# Main.net
KiCad netlist of a schematic drawn in Altium Designer
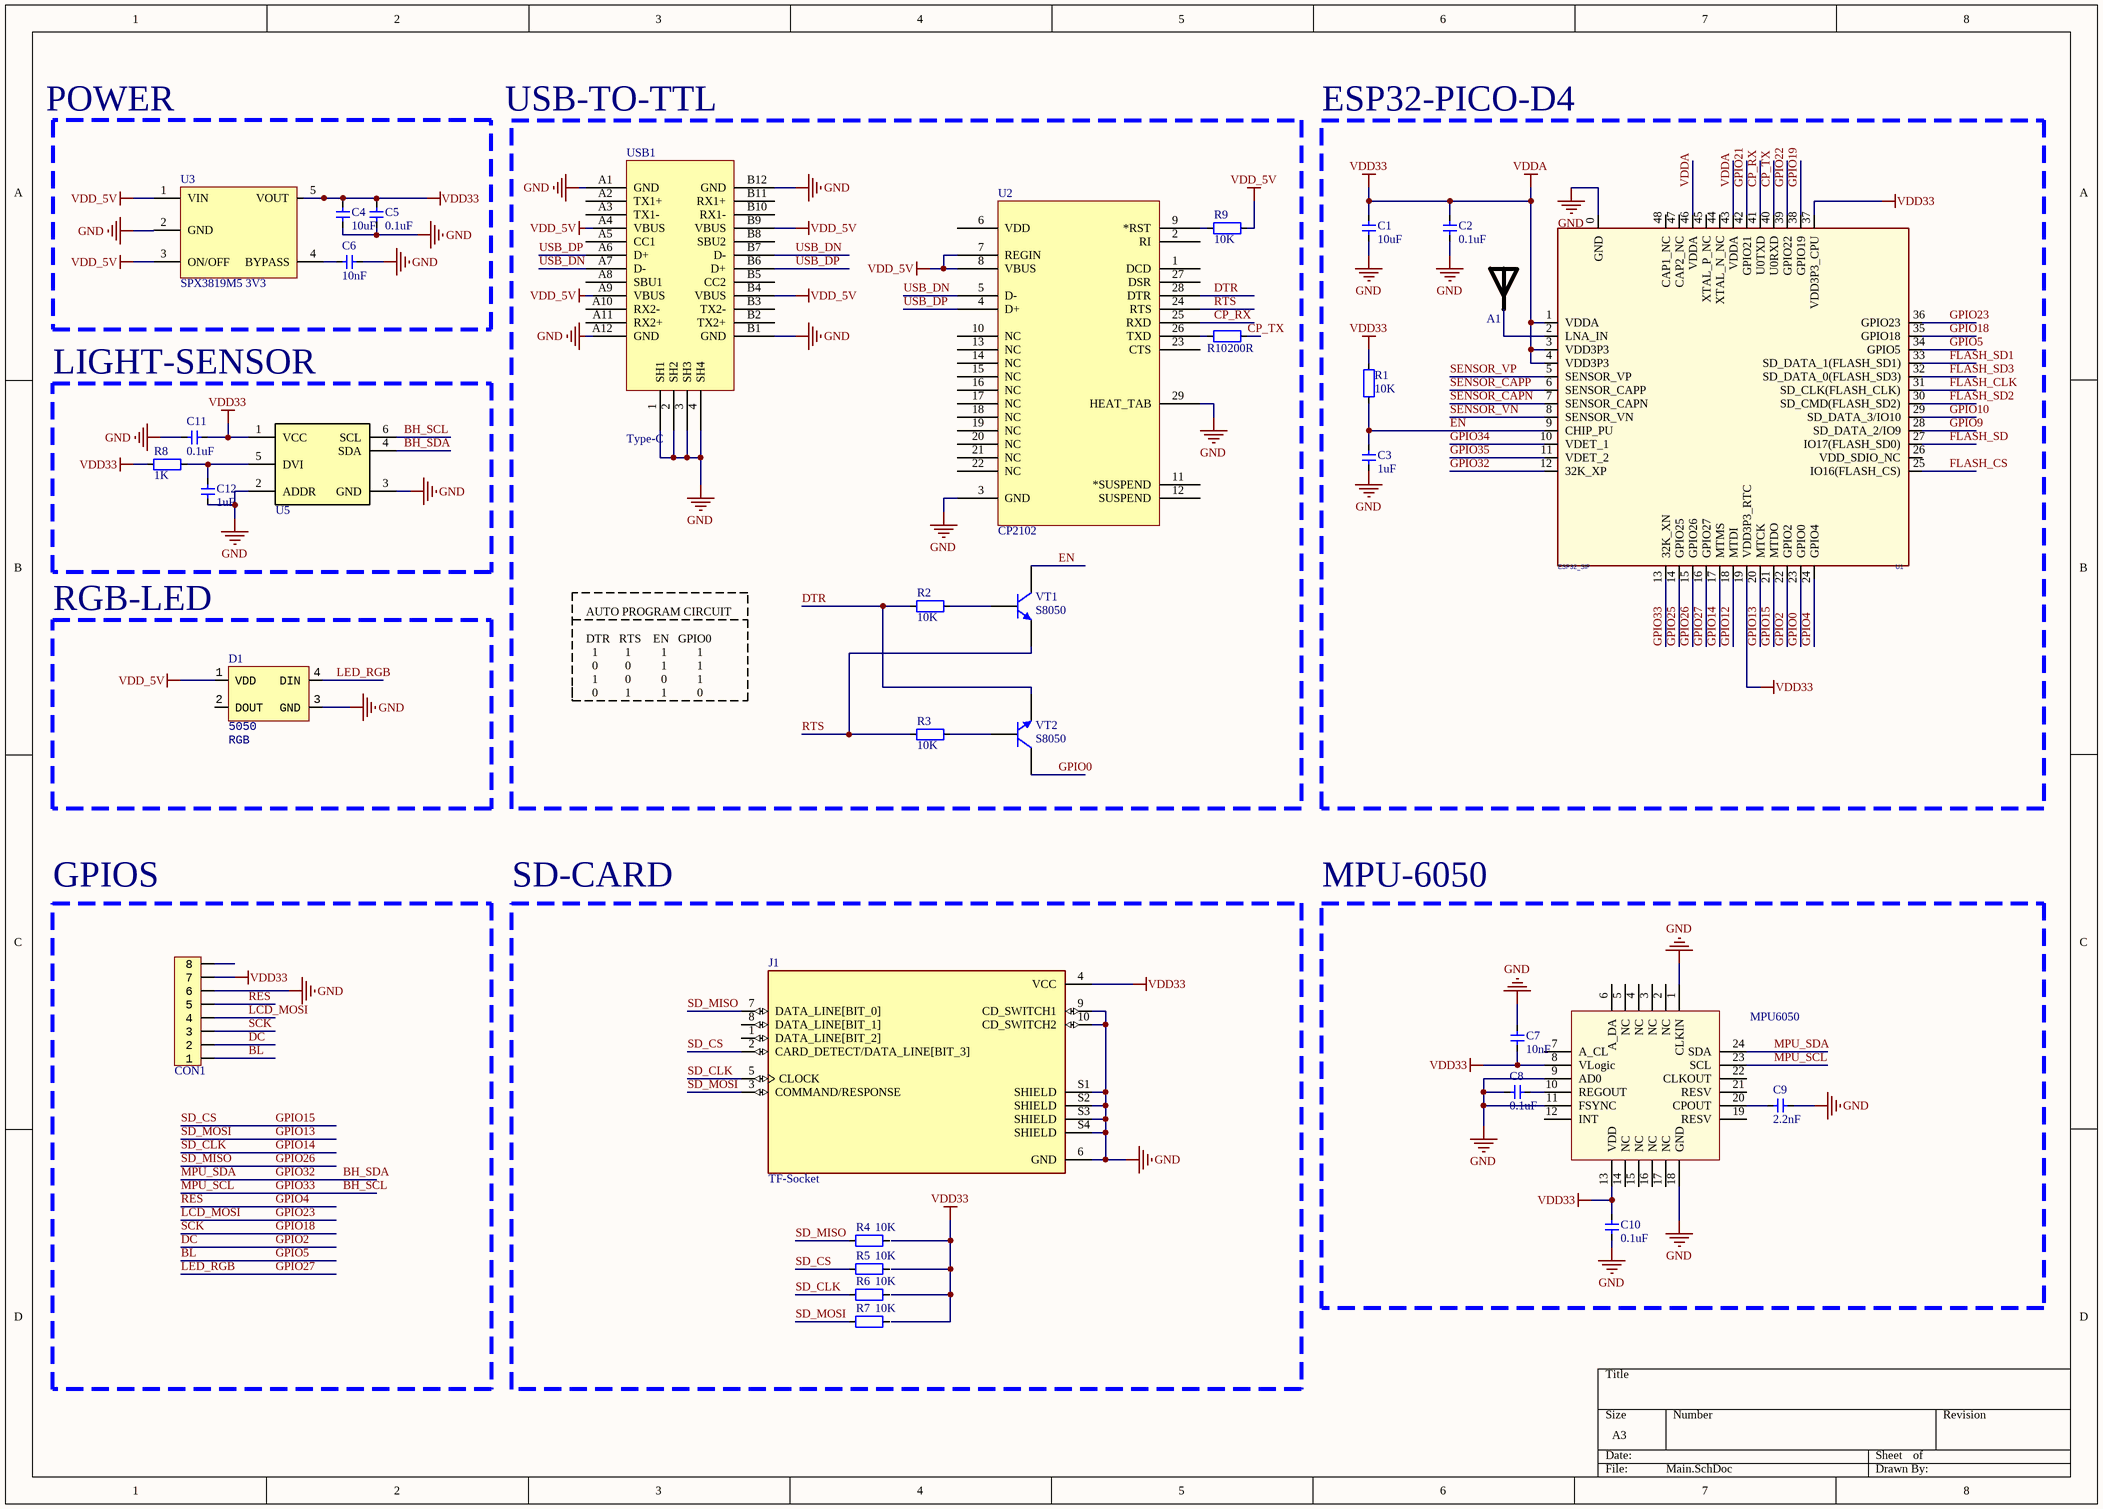
[diagram p0: Main.SchDoc]

(export (version "E")
  (design (tool "Eeschema 10.0.6"))
  (components
    (comp (ref "A1")
      (value "RAINSUN")
      (footprint "ANT-Rainsun-AN5120")
      (libsource (lib "MainBoard") (part "ANT-Rainsun-AP5120"))
    )
    (comp (ref "C1")
      (value "10uF")
      (footprint "CAP_0402")
      (description "Capacitor")
      (libsource (lib "MainBoard") (part "电容-0402_3"))
    )
    (comp (ref "C2")
      (value "0.1uF")
      (footprint "CAP_0402")
      (description "Capacitor")
      (libsource (lib "MainBoard") (part "电容-0402"))
    )
    (comp (ref "C3")
      (value "1uF")
      (footprint "CAP_0402")
      (description "Capacitor")
      (libsource (lib "MainBoard") (part "电容-0402_3"))
    )
    (comp (ref "C4")
      (value "10uF")
      (footprint "CAP_0402")
      (description "Capacitor")
      (libsource (lib "MainBoard") (part "电容-0402_3"))
    )
    (comp (ref "C5")
      (value "0.1uF")
      (footprint "CAP_0402")
      (description "Capacitor")
      (libsource (lib "MainBoard") (part "电容-0402"))
    )
    (comp (ref "C6")
      (value "10nF")
      (footprint "CAP_0402")
      (description "Capacitor")
      (libsource (lib "MainBoard") (part "电容-0402"))
    )
    (comp (ref "C7")
      (value "10nF")
      (footprint "CAP_0402")
      (description "Capacitor")
      (libsource (lib "MainBoard") (part "电容-0402"))
    )
    (comp (ref "C8")
      (value "0.1uF")
      (footprint "CAP_0402")
      (description "Capacitor")
      (libsource (lib "MainBoard") (part "电容-0402"))
    )
    (comp (ref "C9")
      (value "2.2nF")
      (footprint "CAP_0402")
      (description "Capacitor")
      (libsource (lib "MainBoard") (part "电容-0402"))
    )
    (comp (ref "C10")
      (value "0.1uF")
      (footprint "CAP_0402")
      (description "Capacitor")
      (libsource (lib "MainBoard") (part "电容-0402"))
    )
    (comp (ref "C11")
      (value "0.1uF")
      (footprint "CAP_0402")
      (description "Capacitor")
      (libsource (lib "MainBoard") (part "电容-0402"))
    )
    (comp (ref "C12")
      (value "1uF")
      (footprint "CAP_0402")
      (description "Capacitor")
      (libsource (lib "MainBoard") (part "电容-0402"))
    )
    (comp (ref "CON1")
      (value "FFC_0.5_8")
      (footprint "FFC_0.5_8")
      (description "FFC")
      (libsource (lib "ExtendBoard") (part "FFC_0.5_8"))
    )
    (comp (ref "D1")
      (value "RGB")
      (footprint "LED_5050_WS2812B")
      (description "LED")
      (fields (field (name "TYPE") "5050"))
      (libsource (lib "MainBoard") (part "LED_5050_WS2812B"))
    )
    (comp (ref "J1")
      (value "TF-Socket")
      (footprint "TF-Card-Amphenol with TF")
      (description "10 _8 + 2_ Position Card Connector Secure Digital - microSDâ„¢ Surface Mount, Right Angle Gold")
      (fields (field (name "MP") "1140084168") (field (name "MF") "Amphenol Commercial Products"))
      (libsource (lib "MainBoard") (part "TF-Socket"))
    )
    (comp (ref "R1")
      (value "10K")
      (footprint "RES_0402")
      (description "Resistor")
      (libsource (lib "") (part "电阻-0402_1_1"))
    )
    (comp (ref "R2")
      (value "10K")
      (footprint "RES_0402")
      (description "Resistor")
      (libsource (lib "MainBoard") (part "电阻-0402_1"))
    )
    (comp (ref "R3")
      (value "10K")
      (footprint "RES_0402")
      (description "Resistor")
      (libsource (lib "MainBoard") (part "电阻-0402_1"))
    )
    (comp (ref "R4")
      (value "10K")
      (footprint "RES_0402")
      (description "Resistor")
      (libsource (lib "MainBoard") (part "电阻-0402_1"))
    )
    (comp (ref "R5")
      (value "10K")
      (footprint "RES_0402")
      (description "Resistor")
      (libsource (lib "MainBoard") (part "电阻-0402_1"))
    )
    (comp (ref "R6")
      (value "10K")
      (footprint "RES_0402")
      (description "Resistor")
      (libsource (lib "MainBoard") (part "电阻-0402_1"))
    )
    (comp (ref "R7")
      (value "10K")
      (footprint "RES_0402")
      (description "Resistor")
      (libsource (lib "MainBoard") (part "电阻-0402_1"))
    )
    (comp (ref "R8")
      (value "1K")
      (footprint "RES_0402")
      (description "Resistor")
      (libsource (lib "MainBoard") (part "电阻-0402_1"))
    )
    (comp (ref "R9")
      (value "10K")
      (footprint "RES_0402")
      (description "Resistor")
      (libsource (lib "MainBoard") (part "电阻-0402_1"))
    )
    (comp (ref "R10")
      (value "200R")
      (footprint "RES_0402")
      (description "Resistor")
      (libsource (lib "MainBoard") (part "电阻-0402_1"))
    )
    (comp (ref "U1")
      (value "ESP32_SIP")
      (footprint "QFN-48_7X7")
      (libsource (lib "MainBoard") (part "ESP32-PICO"))
    )
    (comp (ref "U2")
      (value "CP2102")
      (footprint "QFN-28")
      (description "USB转TTL")
      (libsource (lib "MainBoard") (part "CP2102"))
    )
    (comp (ref "U3")
      (value "SPX3819M5 3V3")
      (footprint "SOT23-5")
      (description "LDO")
      (libsource (lib "MainBoard") (part "LP2992"))
    )
    (comp (ref "U4")
      (value "MPU6050")
      (footprint "QFN-24")
      (description "六轴传感器")
      (libsource (lib "MainBoard") (part "MPU6050"))
    )
    (comp (ref "U5")
      (value "BH1750FVI-TR")
      (footprint "BH1750FVI")
      (libsource (lib "MainBoard") (part "BH1750FVI-TR"))
    )
    (comp (ref "USB1")
      (value "Type-C")
      (footprint "Type-C-TOP")
      (libsource (lib "MainBoard") (part "USB-Type-C-TOP"))
    )
    (comp (ref "VT1")
      (value "S8050")
      (footprint "SMT_TRIODE_NPN")
      (description "Surface mount NPN transistor, package SOT-23")
      (libsource (lib "MainBoard") (part "SMT_TRIODE_NPN"))
    )
    (comp (ref "VT2")
      (value "S8050")
      (footprint "SMT_TRIODE_NPN")
      (description "Surface mount NPN transistor, package SOT-23")
      (libsource (lib "MainBoard") (part "SMT_TRIODE_NPN"))
    )
  )
  (nets
    (net (code "1") (name "/BH_SCL") (class "Default")
      (node (ref "U1") (pin "13") (pinfunction "32K_XN_13") (pintype "passive"))
      (node (ref "U4") (pin "23") (pinfunction "SCL_23") (pintype "passive"))
      (node (ref "U5") (pin "6") (pinfunction "SCL_6") (pintype "passive"))
    )
    (net (code "2") (name "/BH_SDA") (class "Default")
      (node (ref "U1") (pin "12") (pinfunction "32K_XP_12") (pintype "passive"))
      (node (ref "U4") (pin "24") (pinfunction "SDA_24") (pintype "passive"))
      (node (ref "U5") (pin "4") (pinfunction "SDA_4") (pintype "passive"))
    )
    (net (code "3") (name "/BL") (class "Default")
      (node (ref "CON1") (pin "1") (pinfunction "1_1") (pintype "passive"))
      (node (ref "U1") (pin "34") (pinfunction "GPIO5_34") (pintype "passive"))
    )
    (net (code "4") (name "/CP_RX") (class "Default")
      (node (ref "U1") (pin "41") (pinfunction "U0TXD_41") (pintype "power_in"))
      (node (ref "U2") (pin "25") (pinfunction "RXD_25") (pintype "passive"))
    )
    (net (code "5") (name "/CP_TX") (class "Default")
      (node (ref "R10") (pin "1") (pinfunction "1_1") (pintype "passive"))
      (node (ref "U1") (pin "40") (pinfunction "U0RXD_40") (pintype "power_in"))
    )
    (net (code "6") (name "/DC") (class "Default")
      (node (ref "CON1") (pin "2") (pinfunction "2_2") (pintype "passive"))
      (node (ref "U1") (pin "22") (pinfunction "GPIO2_22") (pintype "passive"))
    )
    (net (code "7") (name "/DTR") (class "Default")
      (node (ref "R2") (pin "2") (pinfunction "2_2") (pintype "passive"))
      (node (ref "U2") (pin "28") (pinfunction "DTR_28") (pintype "passive"))
      (node (ref "VT2") (pin "2") (pinfunction "E_2") (pintype "passive"))
    )
    (net (code "8") (name "/EN") (class "Default")
      (node (ref "C3") (pin "2") (pinfunction "2_2") (pintype "passive"))
      (node (ref "R1") (pin "1") (pinfunction "1_1") (pintype "passive"))
      (node (ref "U1") (pin "9") (pinfunction "CHIP_PU_9") (pintype "passive"))
      (node (ref "VT1") (pin "3") (pinfunction "C_3") (pintype "passive"))
    )
    (net (code "9") (name "/FLASH_CLK") (class "Default")
      (node (ref "U1") (pin "31") (pinfunction "SD_CLK(FLASH_CLK)_31") (pintype "passive"))
    )
    (net (code "10") (name "/FLASH_CS") (class "Default")
      (node (ref "U1") (pin "25") (pinfunction "IO16(FLASH_CS)_25") (pintype "passive"))
    )
    (net (code "11") (name "/FLASH_SD") (class "Default")
      (node (ref "U1") (pin "27") (pinfunction "IO17(FLASH_SD0)_27") (pintype "passive"))
    )
    (net (code "12") (name "/FLASH_SD1") (class "Default")
      (node (ref "U1") (pin "33") (pinfunction "SD_DATA_1(FLASH_SD1)_33") (pintype "passive"))
    )
    (net (code "13") (name "/FLASH_SD2") (class "Default")
      (node (ref "U1") (pin "30") (pinfunction "SD_CMD(FLASH_SD2)_30") (pintype "passive"))
    )
    (net (code "14") (name "/FLASH_SD3") (class "Default")
      (node (ref "U1") (pin "32") (pinfunction "SD_DATA_0(FLASH_SD3)_32") (pintype "passive"))
    )
    (net (code "15") (name "/GPIO0") (class "Default")
      (node (ref "U1") (pin "23") (pinfunction "GPIO0_23") (pintype "passive"))
      (node (ref "VT2") (pin "3") (pinfunction "C_3") (pintype "passive"))
    )
    (net (code "16") (name "/GPIO4") (class "Default")
      (node (ref "CON1") (pin "5") (pinfunction "5_5") (pintype "passive"))
      (node (ref "U1") (pin "24") (pinfunction "GPIO4_24") (pintype "passive"))
    )
    (net (code "17") (name "/GPIO9") (class "Default")
      (node (ref "U1") (pin "28") (pinfunction "SD_DATA_2/IO9_28") (pintype "passive"))
    )
    (net (code "18") (name "/GPIO10") (class "Default")
      (node (ref "U1") (pin "29") (pinfunction "SD_DATA_3/IO10_29") (pintype "passive"))
    )
    (net (code "19") (name "/GPIO12") (class "Default")
      (node (ref "U1") (pin "18") (pinfunction "MTDI_18") (pintype "passive"))
    )
    (net (code "20") (name "/GPIO13") (class "Default")
      (node (ref "J1") (pin "3") (pinfunction "COMMAND/RESPONSE_3") (pintype "bidirectional"))
      (node (ref "R7") (pin "2") (pinfunction "2_2") (pintype "passive"))
      (node (ref "U1") (pin "20") (pinfunction "MTCK_20") (pintype "passive"))
    )
    (net (code "21") (name "/GPIO14") (class "Default")
      (node (ref "J1") (pin "5") (pinfunction "CLOCK_5") (pintype "bidirectional"))
      (node (ref "R6") (pin "2") (pinfunction "2_2") (pintype "passive"))
      (node (ref "U1") (pin "17") (pinfunction "MTMS_17") (pintype "passive"))
    )
    (net (code "22") (name "/GPIO15") (class "Default")
      (node (ref "J1") (pin "2") (pinfunction "CARD_DETECT/DATA_LINE[BIT_3]_2") (pintype "bidirectional"))
      (node (ref "R5") (pin "2") (pinfunction "2_2") (pintype "passive"))
      (node (ref "U1") (pin "21") (pinfunction "MTDO_21") (pintype "passive"))
    )
    (net (code "23") (name "/GPIO18") (class "Default")
      (node (ref "CON1") (pin "3") (pinfunction "3_3") (pintype "passive"))
      (node (ref "U1") (pin "35") (pinfunction "GPIO18_35") (pintype "passive"))
    )
    (net (code "24") (name "/GPIO19") (class "Default")
      (node (ref "U1") (pin "38") (pinfunction "GPIO19_38") (pintype "passive"))
    )
    (net (code "25") (name "/GPIO21") (class "Default")
      (node (ref "U1") (pin "42") (pinfunction "GPIO21_42") (pintype "passive"))
    )
    (net (code "26") (name "/GPIO22") (class "Default")
      (node (ref "U1") (pin "39") (pinfunction "GPIO22_39") (pintype "passive"))
    )
    (net (code "27") (name "/GPIO23") (class "Default")
      (node (ref "CON1") (pin "4") (pinfunction "4_4") (pintype "passive"))
      (node (ref "U1") (pin "36") (pinfunction "GPIO23_36") (pintype "passive"))
    )
    (net (code "28") (name "/GPIO25") (class "Default")
      (node (ref "U1") (pin "14") (pinfunction "GPIO25_14") (pintype "passive"))
    )
    (net (code "29") (name "/GPIO26") (class "Default")
      (node (ref "J1") (pin "7") (pinfunction "DATA_LINE[BIT_0]_7") (pintype "bidirectional"))
      (node (ref "R4") (pin "2") (pinfunction "2_2") (pintype "passive"))
      (node (ref "U1") (pin "15") (pinfunction "GPIO26_15") (pintype "passive"))
    )
    (net (code "30") (name "/GPIO27") (class "Default")
      (node (ref "D1") (pin "4") (pinfunction "DIN_4") (pintype "passive"))
      (node (ref "U1") (pin "16") (pinfunction "GPIO27_16") (pintype "passive"))
    )
    (net (code "31") (name "/GPIO34") (class "Default")
      (node (ref "U1") (pin "10") (pinfunction "VDET_1_10") (pintype "passive"))
    )
    (net (code "32") (name "/GPIO35") (class "Default")
      (node (ref "U1") (pin "11") (pinfunction "VDET_2_11") (pintype "passive"))
    )
    (net (code "33") (name "/RTS") (class "Default")
      (node (ref "R3") (pin "2") (pinfunction "2_2") (pintype "passive"))
      (node (ref "U2") (pin "24") (pinfunction "RTS_24") (pintype "passive"))
      (node (ref "VT1") (pin "2") (pinfunction "E_2") (pintype "passive"))
    )
    (net (code "34") (name "/SENSOR_CAPN") (class "Default")
      (node (ref "U1") (pin "7") (pinfunction "SENSOR_CAPN_7") (pintype "passive"))
    )
    (net (code "35") (name "/SENSOR_CAPP") (class "Default")
      (node (ref "U1") (pin "6") (pinfunction "SENSOR_CAPP_6") (pintype "passive"))
    )
    (net (code "36") (name "/SENSOR_VN") (class "Default")
      (node (ref "U1") (pin "8") (pinfunction "SENSOR_VN_8") (pintype "passive"))
    )
    (net (code "37") (name "/SENSOR_VP") (class "Default")
      (node (ref "U1") (pin "5") (pinfunction "SENSOR_VP_5") (pintype "passive"))
    )
    (net (code "38") (name "/USB_DN") (class "Default")
      (node (ref "U2") (pin "5") (pinfunction "D-_5") (pintype "passive"))
      (node (ref "USB1") (pin "A7") (pinfunction "D-_A7") (pintype "passive"))
      (node (ref "USB1") (pin "B7") (pinfunction "D-_B7") (pintype "passive"))
    )
    (net (code "39") (name "/USB_DP") (class "Default")
      (node (ref "U2") (pin "4") (pinfunction "D+_4") (pintype "passive"))
      (node (ref "USB1") (pin "A6") (pinfunction "D+_A6") (pintype "passive"))
      (node (ref "USB1") (pin "B6") (pinfunction "D+_B6") (pintype "passive"))
    )
    (net (code "40") (name "GND") (class "Default")
      (node (ref "C1") (pin "1") (pinfunction "1_1") (pintype "passive"))
      (node (ref "C10") (pin "1") (pinfunction "1_1") (pintype "passive"))
      (node (ref "C11") (pin "2") (pinfunction "2_2") (pintype "passive"))
      (node (ref "C12") (pin "2") (pinfunction "2_2") (pintype "passive"))
      (node (ref "C2") (pin "1") (pinfunction "1_1") (pintype "passive"))
      (node (ref "C3") (pin "1") (pinfunction "1_1") (pintype "passive"))
      (node (ref "C4") (pin "1") (pinfunction "1_1") (pintype "passive"))
      (node (ref "C5") (pin "1") (pinfunction "1_1") (pintype "passive"))
      (node (ref "C6") (pin "1") (pinfunction "1_1") (pintype "passive"))
      (node (ref "C7") (pin "1") (pinfunction "1_1") (pintype "passive"))
      (node (ref "C8") (pin "2") (pinfunction "2_2") (pintype "passive"))
      (node (ref "C9") (pin "1") (pinfunction "1_1") (pintype "passive"))
      (node (ref "CON1") (pin "6") (pinfunction "6_6") (pintype "passive"))
      (node (ref "D1") (pin "3") (pinfunction "GND_3") (pintype "passive"))
      (node (ref "J1") (pin "10") (pinfunction "CD_SWITCH2_10") (pintype "bidirectional"))
      (node (ref "J1") (pin "6") (pinfunction "GND_6") (pintype "power_in"))
      (node (ref "J1") (pin "9") (pinfunction "CD_SWITCH1_9") (pintype "bidirectional"))
      (node (ref "J1") (pin "S1") (pinfunction "SHIELD_S1") (pintype "passive"))
      (node (ref "J1") (pin "S2") (pinfunction "SHIELD_S2") (pintype "passive"))
      (node (ref "J1") (pin "S3") (pinfunction "SHIELD_S3") (pintype "passive"))
      (node (ref "J1") (pin "S4") (pinfunction "SHIELD_S4") (pintype "passive"))
      (node (ref "U1") (pin "0") (pinfunction "GND_0") (pintype "power_in"))
      (node (ref "U2") (pin "29") (pinfunction "HEAT_TAB_29") (pintype "passive"))
      (node (ref "U2") (pin "3") (pinfunction "GND_3") (pintype "passive"))
      (node (ref "U3") (pin "2") (pinfunction "GND_2") (pintype "passive"))
      (node (ref "U4") (pin "1") (pinfunction "CLKIN_1") (pintype "passive"))
      (node (ref "U4") (pin "11") (pinfunction "FSYNC_11") (pintype "passive"))
      (node (ref "U4") (pin "18") (pinfunction "GND_18") (pintype "passive"))
      (node (ref "U4") (pin "9") (pinfunction "AD0_9") (pintype "passive"))
      (node (ref "U5") (pin "2") (pinfunction "ADDR_2") (pintype "passive"))
      (node (ref "U5") (pin "3") (pinfunction "GND_3") (pintype "passive"))
      (node (ref "USB1") (pin "1") (pinfunction "SH1_1") (pintype "passive"))
      (node (ref "USB1") (pin "2") (pinfunction "SH2_2") (pintype "passive"))
      (node (ref "USB1") (pin "3") (pinfunction "SH3_3") (pintype "passive"))
      (node (ref "USB1") (pin "4") (pinfunction "SH4_4") (pintype "passive"))
      (node (ref "USB1") (pin "A1") (pinfunction "GND_A1") (pintype "passive"))
      (node (ref "USB1") (pin "A12") (pinfunction "GND_A12") (pintype "passive"))
      (node (ref "USB1") (pin "B1") (pinfunction "GND_B1") (pintype "passive"))
      (node (ref "USB1") (pin "B12") (pinfunction "GND_B12") (pintype "passive"))
    )
    (net (code "41") (name "Net-(U1-LNA_IN)") (class "Default")
      (node (ref "A1") (pin "1") (pinfunction "1_1") (pintype "passive"))
      (node (ref "U1") (pin "2") (pinfunction "LNA_IN_2") (pintype "passive"))
    )
    (net (code "42") (name "Net-(U2-*RST)") (class "Default")
      (node (ref "R9") (pin "2") (pinfunction "2_2") (pintype "passive"))
      (node (ref "U2") (pin "9") (pinfunction "*RST_9") (pintype "passive"))
    )
    (net (code "43") (name "Net-(U2-TXD)") (class "Default")
      (node (ref "R10") (pin "2") (pinfunction "2_2") (pintype "passive"))
      (node (ref "U2") (pin "26") (pinfunction "TXD_26") (pintype "passive"))
    )
    (net (code "44") (name "Net-(U3-BYPASS)") (class "Default")
      (node (ref "C6") (pin "2") (pinfunction "2_2") (pintype "passive"))
      (node (ref "U3") (pin "4") (pinfunction "BYPASS_4") (pintype "passive"))
    )
    (net (code "45") (name "Net-(U4-CPOUT)") (class "Default")
      (node (ref "C9") (pin "2") (pinfunction "2_2") (pintype "passive"))
      (node (ref "U4") (pin "20") (pinfunction "CPOUT_20") (pintype "passive"))
    )
    (net (code "46") (name "Net-(U4-REGOUT)") (class "Default")
      (node (ref "C8") (pin "1") (pinfunction "1_1") (pintype "passive"))
      (node (ref "U4") (pin "10") (pinfunction "REGOUT_10") (pintype "passive"))
    )
    (net (code "47") (name "Net-(U5-DVI)") (class "Default")
      (node (ref "C12") (pin "1") (pinfunction "1_1") (pintype "passive"))
      (node (ref "R8") (pin "1") (pinfunction "1_1") (pintype "passive"))
      (node (ref "U5") (pin "5") (pinfunction "DVI_5") (pintype "passive"))
    )
    (net (code "48") (name "Net-(VT1-B)") (class "Default")
      (node (ref "R2") (pin "1") (pinfunction "1_1") (pintype "passive"))
      (node (ref "VT1") (pin "1") (pinfunction "B_1") (pintype "passive"))
    )
    (net (code "49") (name "Net-(VT2-B)") (class "Default")
      (node (ref "R3") (pin "1") (pinfunction "1_1") (pintype "passive"))
      (node (ref "VT2") (pin "1") (pinfunction "B_1") (pintype "passive"))
    )
    (net (code "50") (name "VDD33") (class "Default")
      (node (ref "C1") (pin "2") (pinfunction "2_2") (pintype "passive"))
      (node (ref "C10") (pin "2") (pinfunction "2_2") (pintype "passive"))
      (node (ref "C11") (pin "1") (pinfunction "1_1") (pintype "passive"))
      (node (ref "C2") (pin "2") (pinfunction "2_2") (pintype "passive"))
      (node (ref "C4") (pin "2") (pinfunction "2_2") (pintype "passive"))
      (node (ref "C5") (pin "2") (pinfunction "2_2") (pintype "passive"))
      (node (ref "C7") (pin "2") (pinfunction "2_2") (pintype "passive"))
      (node (ref "CON1") (pin "7") (pinfunction "7_7") (pintype "passive"))
      (node (ref "J1") (pin "4") (pinfunction "VCC_4") (pintype "power_in"))
      (node (ref "R1") (pin "2") (pinfunction "2_2") (pintype "passive"))
      (node (ref "R8") (pin "2") (pinfunction "2_2") (pintype "passive"))
      (node (ref "U1") (pin "1") (pinfunction "VDDA_1") (pintype "power_in"))
      (node (ref "U1") (pin "19") (pinfunction "VDD3P3_RTC_19") (pintype "power_in"))
      (node (ref "U1") (pin "3") (pinfunction "VDD3P3_3") (pintype "power_in"))
      (node (ref "U1") (pin "37") (pinfunction "VDD3P3_CPU_37") (pintype "power_in"))
      (node (ref "U1") (pin "4") (pinfunction "VDD3P3_4") (pintype "power_in"))
      (node (ref "U1") (pin "43") (pinfunction "VDDA_43") (pintype "power_in"))
      (node (ref "U1") (pin "46") (pinfunction "VDDA_46") (pintype "power_in"))
      (node (ref "U3") (pin "5") (pinfunction "VOUT_5") (pintype "passive"))
      (node (ref "U4") (pin "13") (pinfunction "VDD_13") (pintype "passive"))
      (node (ref "U4") (pin "8") (pinfunction "VLogic_8") (pintype "passive"))
      (node (ref "U5") (pin "1") (pinfunction "VCC_1") (pintype "passive"))
    )
    (net (code "51") (name "VDD_5V") (class "Default")
      (node (ref "D1") (pin "1") (pinfunction "VDD_1") (pintype "passive"))
      (node (ref "R9") (pin "1") (pinfunction "1_1") (pintype "passive"))
      (node (ref "U2") (pin "7") (pinfunction "REGIN_7") (pintype "passive"))
      (node (ref "U2") (pin "8") (pinfunction "VBUS_8") (pintype "passive"))
      (node (ref "U3") (pin "1") (pinfunction "VIN_1") (pintype "passive"))
      (node (ref "U3") (pin "3") (pinfunction "ON/OFF_3") (pintype "passive"))
      (node (ref "USB1") (pin "A4") (pinfunction "VBUS_A4") (pintype "passive"))
      (node (ref "USB1") (pin "A9") (pinfunction "VBUS_A9") (pintype "passive"))
      (node (ref "USB1") (pin "B4") (pinfunction "VBUS_B4") (pintype "passive"))
      (node (ref "USB1") (pin "B9") (pinfunction "VBUS_B9") (pintype "passive"))
    )
    (net (code "52") (name "unconnected-(CON1-Pad8)") (class "Default")
      (node (ref "CON1") (pin "8") (pinfunction "8_8") (pintype "passive"))
    )
    (net (code "53") (name "unconnected-(D1-DOUT-Pad2)") (class "Default")
      (node (ref "D1") (pin "2") (pinfunction "DOUT_2") (pintype "passive"))
    )
    (net (code "54") (name "unconnected-(J1-DATA_LINE[BIT_1]-Pad8)") (class "Default")
      (node (ref "J1") (pin "8") (pinfunction "DATA_LINE[BIT_1]_8") (pintype "bidirectional"))
    )
    (net (code "55") (name "unconnected-(J1-DATA_LINE[BIT_2]-Pad1)") (class "Default")
      (node (ref "J1") (pin "1") (pinfunction "DATA_LINE[BIT_2]_1") (pintype "bidirectional"))
    )
    (net (code "56") (name "unconnected-(R4-Pad1)") (class "Default")
      (node (ref "R4") (pin "1") (pinfunction "1_1") (pintype "passive"))
    )
    (net (code "57") (name "unconnected-(R5-Pad1)") (class "Default")
      (node (ref "R5") (pin "1") (pinfunction "1_1") (pintype "passive"))
    )
    (net (code "58") (name "unconnected-(R6-Pad1)") (class "Default")
      (node (ref "R6") (pin "1") (pinfunction "1_1") (pintype "passive"))
    )
    (net (code "59") (name "unconnected-(R7-Pad1)") (class "Default")
      (node (ref "R7") (pin "1") (pinfunction "1_1") (pintype "passive"))
    )
    (net (code "60") (name "unconnected-(U1-CAP1_NC-Pad48)") (class "Default")
      (node (ref "U1") (pin "48") (pinfunction "CAP1_NC_48") (pintype "passive"))
    )
    (net (code "61") (name "unconnected-(U1-CAP2_NC-Pad47)") (class "Default")
      (node (ref "U1") (pin "47") (pinfunction "CAP2_NC_47") (pintype "passive"))
    )
    (net (code "62") (name "unconnected-(U1-VDD_SDIO_NC-Pad26)") (class "Default")
      (node (ref "U1") (pin "26") (pinfunction "VDD_SDIO_NC_26") (pintype "passive"))
    )
    (net (code "63") (name "unconnected-(U1-XTAL_N_NC-Pad44)") (class "Default")
      (node (ref "U1") (pin "44") (pinfunction "XTAL_N_NC_44") (pintype "passive"))
    )
    (net (code "64") (name "unconnected-(U1-XTAL_P_NC-Pad45)") (class "Default")
      (node (ref "U1") (pin "45") (pinfunction "XTAL_P_NC_45") (pintype "passive"))
    )
    (net (code "65") (name "unconnected-(U2-*SUSPEND-Pad11)") (class "Default")
      (node (ref "U2") (pin "11") (pinfunction "*SUSPEND_11") (pintype "passive"))
    )
    (net (code "66") (name "unconnected-(U2-CTS-Pad23)") (class "Default")
      (node (ref "U2") (pin "23") (pinfunction "CTS_23") (pintype "passive"))
    )
    (net (code "67") (name "unconnected-(U2-DCD-Pad1)") (class "Default")
      (node (ref "U2") (pin "1") (pinfunction "DCD_1") (pintype "passive"))
    )
    (net (code "68") (name "unconnected-(U2-DSR-Pad27)") (class "Default")
      (node (ref "U2") (pin "27") (pinfunction "DSR_27") (pintype "passive"))
    )
    (net (code "69") (name "unconnected-(U2-NC-Pad10)") (class "Default")
      (node (ref "U2") (pin "10") (pinfunction "NC_10") (pintype "passive"))
    )
    (net (code "70") (name "unconnected-(U2-NC-Pad13)") (class "Default")
      (node (ref "U2") (pin "13") (pinfunction "NC_13") (pintype "passive"))
    )
    (net (code "71") (name "unconnected-(U2-NC-Pad14)") (class "Default")
      (node (ref "U2") (pin "14") (pinfunction "NC_14") (pintype "passive"))
    )
    (net (code "72") (name "unconnected-(U2-NC-Pad15)") (class "Default")
      (node (ref "U2") (pin "15") (pinfunction "NC_15") (pintype "passive"))
    )
    (net (code "73") (name "unconnected-(U2-NC-Pad16)") (class "Default")
      (node (ref "U2") (pin "16") (pinfunction "NC_16") (pintype "passive"))
    )
    (net (code "74") (name "unconnected-(U2-NC-Pad17)") (class "Default")
      (node (ref "U2") (pin "17") (pinfunction "NC_17") (pintype "passive"))
    )
    (net (code "75") (name "unconnected-(U2-NC-Pad18)") (class "Default")
      (node (ref "U2") (pin "18") (pinfunction "NC_18") (pintype "passive"))
    )
    (net (code "76") (name "unconnected-(U2-NC-Pad19)") (class "Default")
      (node (ref "U2") (pin "19") (pinfunction "NC_19") (pintype "passive"))
    )
    (net (code "77") (name "unconnected-(U2-NC-Pad20)") (class "Default")
      (node (ref "U2") (pin "20") (pinfunction "NC_20") (pintype "passive"))
    )
    (net (code "78") (name "unconnected-(U2-NC-Pad21)") (class "Default")
      (node (ref "U2") (pin "21") (pinfunction "NC_21") (pintype "passive"))
    )
    (net (code "79") (name "unconnected-(U2-NC-Pad22)") (class "Default")
      (node (ref "U2") (pin "22") (pinfunction "NC_22") (pintype "passive"))
    )
    (net (code "80") (name "unconnected-(U2-RI-Pad2)") (class "Default")
      (node (ref "U2") (pin "2") (pinfunction "RI_2") (pintype "passive"))
    )
    (net (code "81") (name "unconnected-(U2-SUSPEND-Pad12)") (class "Default")
      (node (ref "U2") (pin "12") (pinfunction "SUSPEND_12") (pintype "passive"))
    )
    (net (code "82") (name "unconnected-(U2-VDD-Pad6)") (class "Default")
      (node (ref "U2") (pin "6") (pinfunction "VDD_6") (pintype "passive"))
    )
    (net (code "83") (name "unconnected-(U4-A_CL-Pad7)") (class "Default")
      (node (ref "U4") (pin "7") (pinfunction "A_CL_7") (pintype "passive"))
    )
    (net (code "84") (name "unconnected-(U4-A_DA-Pad6)") (class "Default")
      (node (ref "U4") (pin "6") (pinfunction "A_DA_6") (pintype "passive"))
    )
    (net (code "85") (name "unconnected-(U4-CLKOUT-Pad22)") (class "Default")
      (node (ref "U4") (pin "22") (pinfunction "CLKOUT_22") (pintype "passive"))
    )
    (net (code "86") (name "unconnected-(U4-INT-Pad12)") (class "Default")
      (node (ref "U4") (pin "12") (pinfunction "INT_12") (pintype "passive"))
    )
    (net (code "87") (name "unconnected-(U4-NC-Pad2)") (class "Default")
      (node (ref "U4") (pin "2") (pinfunction "NC_2") (pintype "passive"))
    )
    (net (code "88") (name "unconnected-(U4-NC-Pad3)") (class "Default")
      (node (ref "U4") (pin "3") (pinfunction "NC_3") (pintype "passive"))
    )
    (net (code "89") (name "unconnected-(U4-NC-Pad4)") (class "Default")
      (node (ref "U4") (pin "4") (pinfunction "NC_4") (pintype "passive"))
    )
    (net (code "90") (name "unconnected-(U4-NC-Pad5)") (class "Default")
      (node (ref "U4") (pin "5") (pinfunction "NC_5") (pintype "passive"))
    )
    (net (code "91") (name "unconnected-(U4-NC-Pad14)") (class "Default")
      (node (ref "U4") (pin "14") (pinfunction "NC_14") (pintype "passive"))
    )
    (net (code "92") (name "unconnected-(U4-NC-Pad15)") (class "Default")
      (node (ref "U4") (pin "15") (pinfunction "NC_15") (pintype "passive"))
    )
    (net (code "93") (name "unconnected-(U4-NC-Pad16)") (class "Default")
      (node (ref "U4") (pin "16") (pinfunction "NC_16") (pintype "passive"))
    )
    (net (code "94") (name "unconnected-(U4-NC-Pad17)") (class "Default")
      (node (ref "U4") (pin "17") (pinfunction "NC_17") (pintype "passive"))
    )
    (net (code "95") (name "unconnected-(U4-RESV-Pad19)") (class "Default")
      (node (ref "U4") (pin "19") (pinfunction "RESV_19") (pintype "passive"))
    )
    (net (code "96") (name "unconnected-(U4-RESV-Pad21)") (class "Default")
      (node (ref "U4") (pin "21") (pinfunction "RESV_21") (pintype "passive"))
    )
    (net (code "97") (name "unconnected-(USB1-CC1-PadA5)") (class "Default")
      (node (ref "USB1") (pin "A5") (pinfunction "CC1_A5") (pintype "passive"))
    )
    (net (code "98") (name "unconnected-(USB1-CC2-PadB5)") (class "Default")
      (node (ref "USB1") (pin "B5") (pinfunction "CC2_B5") (pintype "passive"))
    )
    (net (code "99") (name "unconnected-(USB1-RX1+-PadB11)") (class "Default")
      (node (ref "USB1") (pin "B11") (pinfunction "RX1+_B11") (pintype "passive"))
    )
    (net (code "100") (name "unconnected-(USB1-RX1--PadB10)") (class "Default")
      (node (ref "USB1") (pin "B10") (pinfunction "RX1-_B10") (pintype "passive"))
    )
    (net (code "101") (name "unconnected-(USB1-RX2+-PadA11)") (class "Default")
      (node (ref "USB1") (pin "A11") (pinfunction "RX2+_A11") (pintype "passive"))
    )
    (net (code "102") (name "unconnected-(USB1-RX2--PadA10)") (class "Default")
      (node (ref "USB1") (pin "A10") (pinfunction "RX2-_A10") (pintype "passive"))
    )
    (net (code "103") (name "unconnected-(USB1-SBU1-PadA8)") (class "Default")
      (node (ref "USB1") (pin "A8") (pinfunction "SBU1_A8") (pintype "passive"))
    )
    (net (code "104") (name "unconnected-(USB1-SBU2-PadB8)") (class "Default")
      (node (ref "USB1") (pin "B8") (pinfunction "SBU2_B8") (pintype "passive"))
    )
    (net (code "105") (name "unconnected-(USB1-TX1+-PadA2)") (class "Default")
      (node (ref "USB1") (pin "A2") (pinfunction "TX1+_A2") (pintype "passive"))
    )
    (net (code "106") (name "unconnected-(USB1-TX1--PadA3)") (class "Default")
      (node (ref "USB1") (pin "A3") (pinfunction "TX1-_A3") (pintype "passive"))
    )
    (net (code "107") (name "unconnected-(USB1-TX2+-PadB2)") (class "Default")
      (node (ref "USB1") (pin "B2") (pinfunction "TX2+_B2") (pintype "passive"))
    )
    (net (code "108") (name "unconnected-(USB1-TX2--PadB3)") (class "Default")
      (node (ref "USB1") (pin "B3") (pinfunction "TX2-_B3") (pintype "passive"))
    )
  )
)
